# ELEKTRA-PMIC_v0_2-Ful_frame_shield_-35X2.net
KiCad netlist of a schematic drawn in EAGLE
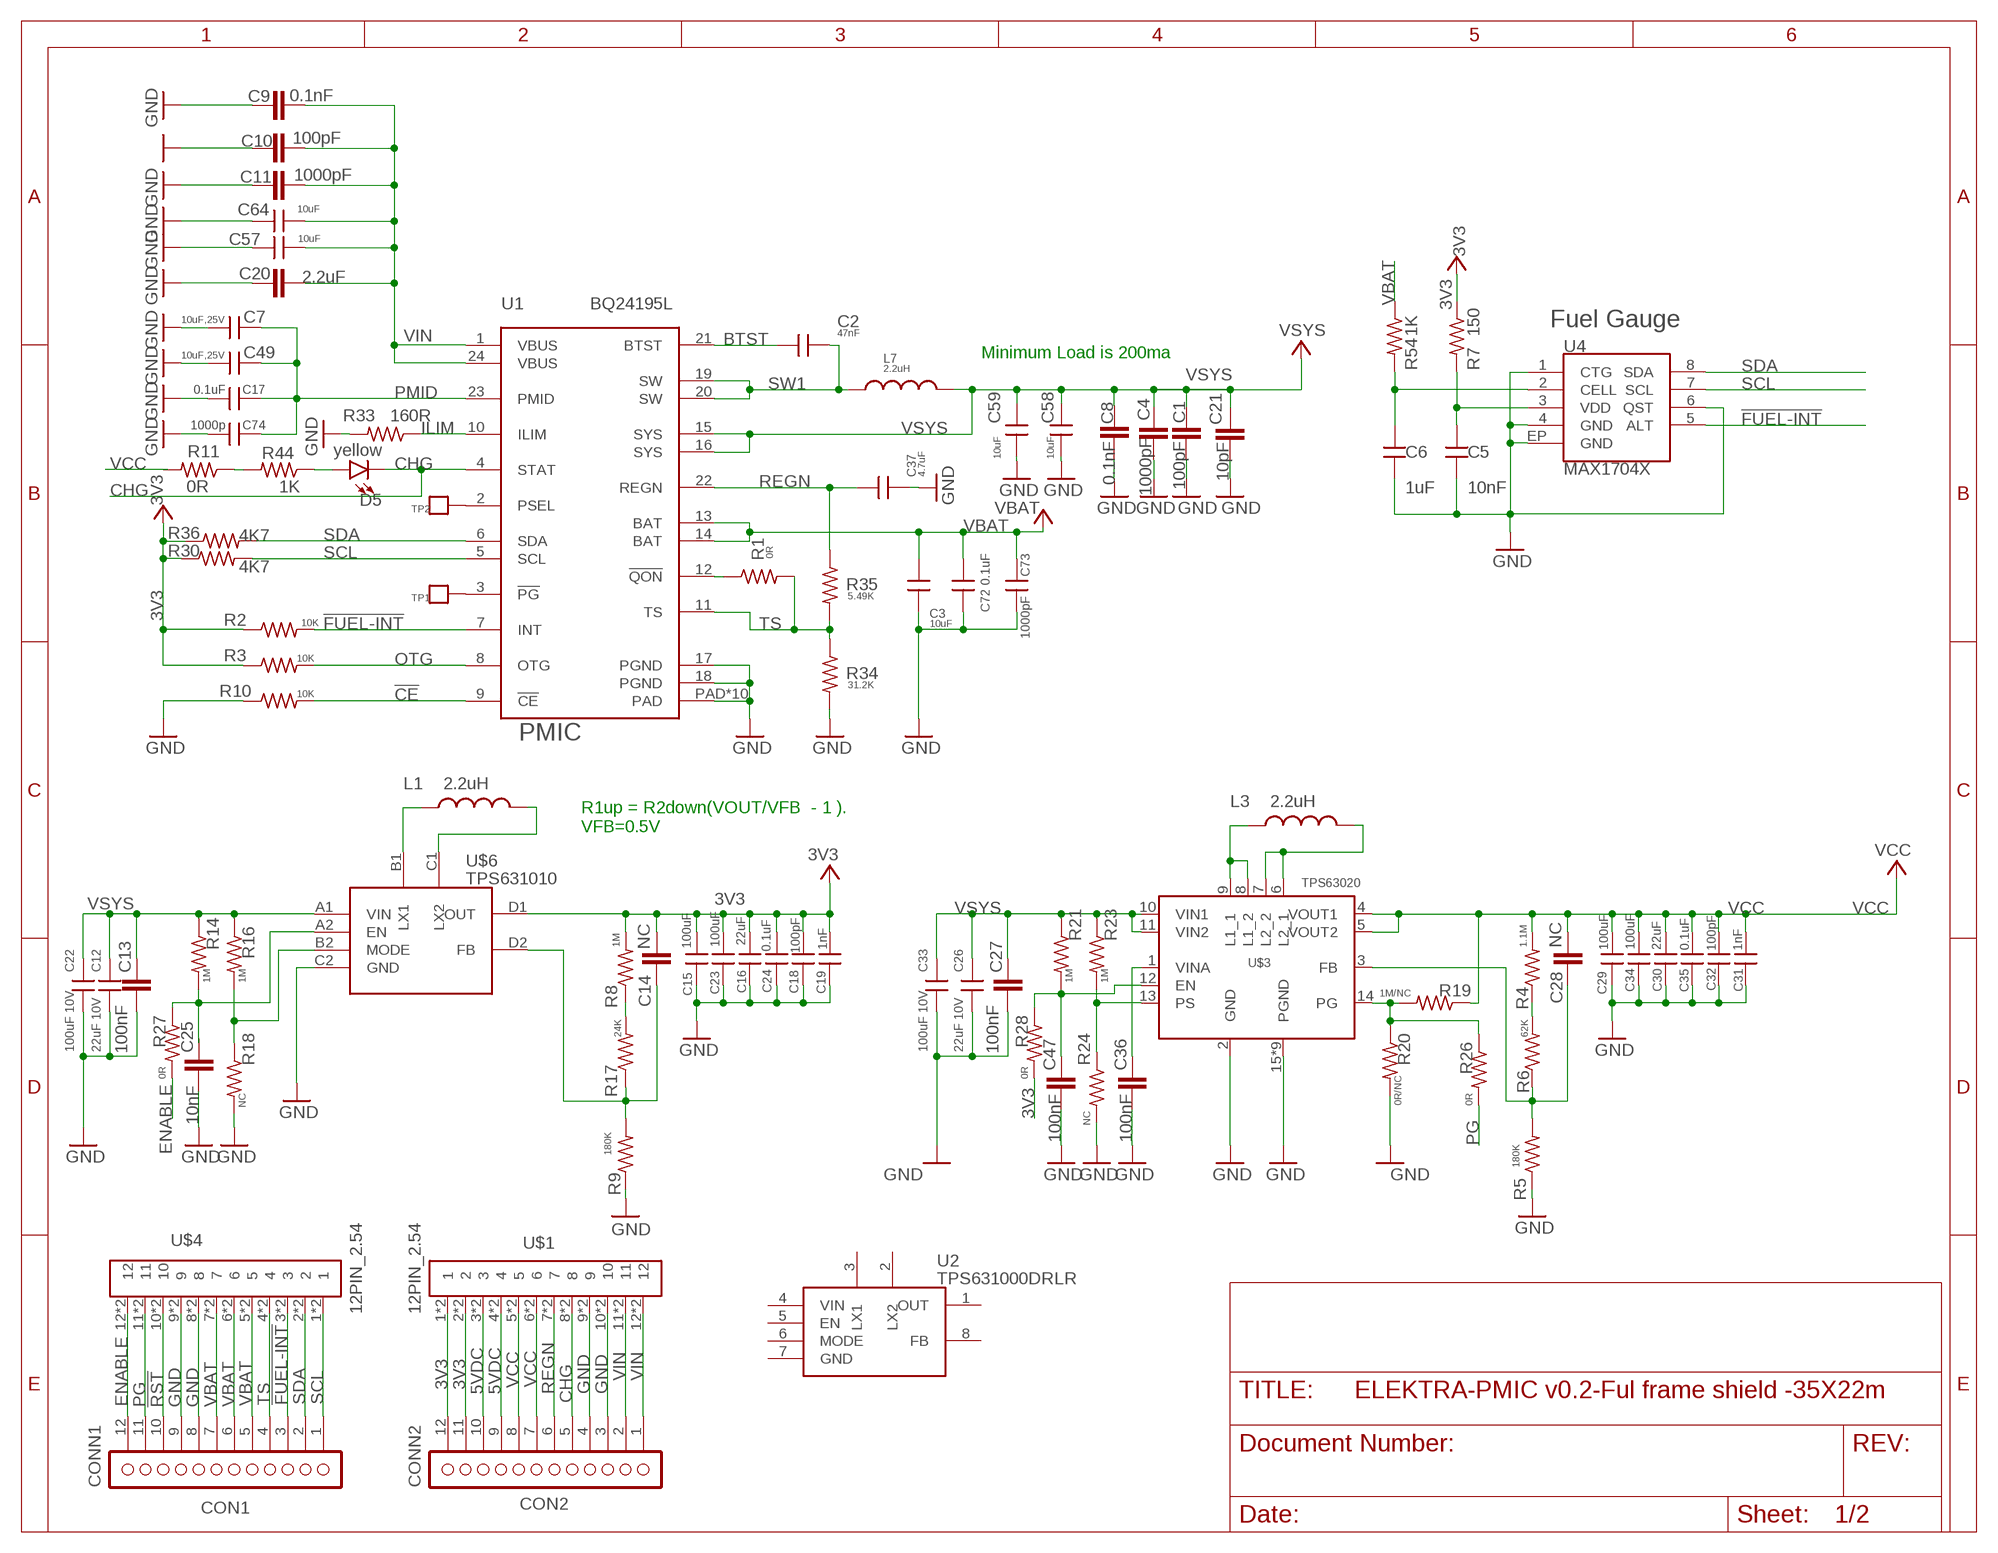
[diagram p0: schematic, sheet 1]

(export (version "E")
  (design (tool "Eeschema 10.0.6"))
  (components
    (comp (ref "C1")
      (value "100pF")
      (footprint "eagle-import:C0402_B")
      (libsource (lib "eagle-import") (part "CAP_1"))
    )
    (comp (ref "C2")
      (value "47nF")
      (footprint "eagle-import:C-0402")
      (libsource (lib "eagle-import") (part "particle SZ_CAP0402"))
    )
    (comp (ref "C3")
      (value "10uF")
      (footprint "eagle-import:C0603")
      (libsource (lib "eagle-import") (part "particle SZ_CAPC0603"))
    )
    (comp (ref "C4")
      (value "1000pF")
      (footprint "eagle-import:C0402_B")
      (libsource (lib "eagle-import") (part "CAP_1"))
    )
    (comp (ref "C5")
      (value "10nF")
      (footprint "eagle-import:C0402")
      (libsource (lib "eagle-import") (part "particle SZ_CAP0402A"))
    )
    (comp (ref "C6")
      (value "1uF")
      (footprint "eagle-import:C0402")
      (libsource (lib "eagle-import") (part "particle SZ_CAP0402A"))
    )
    (comp (ref "C7")
      (value "10uF,25V")
      (footprint "eagle-import:C-0603A")
      (libsource (lib "eagle-import") (part "particle SZ_CAP0603A"))
    )
    (comp (ref "C8")
      (value "0.1nF")
      (footprint "eagle-import:C0402_B")
      (libsource (lib "eagle-import") (part "CAP_1"))
    )
    (comp (ref "C9")
      (value "0.1nF")
      (footprint "eagle-import:C0402_B")
      (libsource (lib "eagle-import") (part "CAP_1"))
    )
    (comp (ref "C10")
      (value "100pF")
      (footprint "eagle-import:C0402_B")
      (libsource (lib "eagle-import") (part "CAP_1"))
    )
    (comp (ref "C11")
      (value "1000pF")
      (footprint "eagle-import:C0402_B")
      (libsource (lib "eagle-import") (part "CAP_1"))
    )
    (comp (ref "C12")
      (value "22uF 10V")
      (footprint "eagle-import:C0805")
      (libsource (lib "eagle-import") (part "particle SZ_21650216_CAPC0805"))
    )
    (comp (ref "C13")
      (value "100nF")
      (footprint "eagle-import:C0402_B")
      (libsource (lib "eagle-import") (part "CAP_1"))
    )
    (comp (ref "C14")
      (value "NC")
      (footprint "eagle-import:C0402_B")
      (libsource (lib "eagle-import") (part "CAP_1"))
    )
    (comp (ref "C15")
      (value "100uF")
      (footprint "eagle-import:C1206")
      (libsource (lib "eagle-import") (part "particle SZ_21650216_CAPC1206"))
    )
    (comp (ref "C16")
      (value "22uF")
      (footprint "eagle-import:C-0603A")
      (libsource (lib "eagle-import") (part "particle SZ_21650216_CAP0603A"))
    )
    (comp (ref "C17")
      (value "0.1uF")
      (footprint "eagle-import:C0402")
      (libsource (lib "eagle-import") (part "CAP0402A"))
    )
    (comp (ref "C18")
      (value "100pF")
      (footprint "eagle-import:C0402")
      (libsource (lib "eagle-import") (part "particle SZ_CAP0402A"))
    )
    (comp (ref "C19")
      (value "1nF")
      (footprint "eagle-import:C0402")
      (libsource (lib "eagle-import") (part "particle SZ_CAP0402A"))
    )
    (comp (ref "C20")
      (value "2.2uF")
      (footprint "eagle-import:C0402_B")
      (libsource (lib "eagle-import") (part "CAP_1"))
    )
    (comp (ref "C21")
      (value "10pF")
      (footprint "eagle-import:C0402_B")
      (libsource (lib "eagle-import") (part "CAP_1"))
    )
    (comp (ref "C22")
      (value "100uF 10V")
      (footprint "eagle-import:C1206")
      (libsource (lib "eagle-import") (part "particle SZ_21650216_CAPC1206"))
    )
    (comp (ref "C23")
      (value "100uF")
      (footprint "eagle-import:C1206")
      (libsource (lib "eagle-import") (part "particle SZ_21650216_CAPC1206"))
    )
    (comp (ref "C24")
      (value "0.1uF")
      (footprint "eagle-import:C0402")
      (libsource (lib "eagle-import") (part "particle SZ_CAP0402A"))
    )
    (comp (ref "C25")
      (value "10nF")
      (footprint "eagle-import:C0402_B")
      (libsource (lib "eagle-import") (part "CAP_1"))
    )
    (comp (ref "C26")
      (value "22uF 10V")
      (footprint "eagle-import:C0805")
      (libsource (lib "eagle-import") (part "particle SZ_21650216_CAPC0805"))
    )
    (comp (ref "C27")
      (value "100nF")
      (footprint "eagle-import:C0402_B")
      (libsource (lib "eagle-import") (part "CAP_1"))
    )
    (comp (ref "C28")
      (value "NC")
      (footprint "eagle-import:C0402_B")
      (libsource (lib "eagle-import") (part "CAP_1"))
    )
    (comp (ref "C29")
      (value "100uF")
      (footprint "eagle-import:C1206")
      (libsource (lib "eagle-import") (part "particle SZ_21650216_CAPC1206"))
    )
    (comp (ref "C30")
      (value "22uF")
      (footprint "eagle-import:C-0603A")
      (libsource (lib "eagle-import") (part "particle SZ_21650216_CAP0603A"))
    )
    (comp (ref "C31")
      (value "1nF")
      (footprint "eagle-import:C0402")
      (libsource (lib "eagle-import") (part "particle SZ_CAP0402A"))
    )
    (comp (ref "C32")
      (value "100pF")
      (footprint "eagle-import:C0402")
      (libsource (lib "eagle-import") (part "particle SZ_CAP0402A"))
    )
    (comp (ref "C33")
      (value "100uF 10V")
      (footprint "eagle-import:C1206")
      (libsource (lib "eagle-import") (part "particle SZ_21650216_CAPC1206"))
    )
    (comp (ref "C34")
      (value "100uF")
      (footprint "eagle-import:C1206")
      (libsource (lib "eagle-import") (part "particle SZ_21650216_CAPC1206"))
    )
    (comp (ref "C35")
      (value "0.1uF")
      (footprint "eagle-import:C0402")
      (libsource (lib "eagle-import") (part "particle SZ_CAP0402A"))
    )
    (comp (ref "C36")
      (value "100nF")
      (footprint "eagle-import:C0402_B")
      (libsource (lib "eagle-import") (part "CAP_1"))
    )
    (comp (ref "C37")
      (value "4.7uF")
      (footprint "eagle-import:C0402")
      (libsource (lib "eagle-import") (part "particle SZ_CAP0402A"))
    )
    (comp (ref "C47")
      (value "100nF")
      (footprint "eagle-import:C0402_B")
      (libsource (lib "eagle-import") (part "CAP_1"))
    )
    (comp (ref "C49")
      (value "10uF,25V")
      (footprint "eagle-import:C-0603A")
      (libsource (lib "eagle-import") (part "particle SZ_CAP0603A"))
    )
    (comp (ref "C57")
      (value "10uF")
      (footprint "eagle-import:C-0603A")
      (libsource (lib "eagle-import") (part "particle SZ_CAP0603A"))
    )
    (comp (ref "C58")
      (value "10uF")
      (footprint "eagle-import:C-0603A")
      (libsource (lib "eagle-import") (part "particle SZ_CAP0603A"))
    )
    (comp (ref "C59")
      (value "10uF")
      (footprint "eagle-import:C-0603A")
      (libsource (lib "eagle-import") (part "particle SZ_CAP0603A"))
    )
    (comp (ref "C64")
      (value "10uF")
      (footprint "eagle-import:C-0603A")
      (libsource (lib "eagle-import") (part "particle SZ_CAP0603A"))
    )
    (comp (ref "C72")
      (value "0.1uF")
      (footprint "eagle-import:C-0402")
      (libsource (lib "eagle-import") (part "particle SZ_CAP0402"))
    )
    (comp (ref "C73")
      (value "1000pF")
      (footprint "eagle-import:C-0402")
      (libsource (lib "eagle-import") (part "particle SZ_CAP0402"))
    )
    (comp (ref "C74")
      (value "1000p")
      (footprint "eagle-import:C-0402")
      (libsource (lib "eagle-import") (part "particle SZ_CAP0402"))
    )
    (comp (ref "CONN1")
      (value "CON1")
      (footprint "eagle-import:1X12_SMD_STRAIGHT")
      (libsource (lib "eagle-import") (part "CONN12"))
    )
    (comp (ref "CONN2")
      (value "CON2")
      (footprint "eagle-import:1X12_SMD_STRAIGHT")
      (libsource (lib "eagle-import") (part "CONN12"))
    )
    (comp (ref "D5")
      (value "yellow")
      (footprint "eagle-import:LED-0603")
      (libsource (lib "eagle-import") (part "LED-RED0603"))
    )
    (comp (ref "L1")
      (value "2.2uH")
      (footprint "eagle-import:INDUCTOR-VLS-E")
      (libsource (lib "eagle-import") (part "INDUCTOR-SPARKFUNVLS3012ET-4R7M"))
    )
    (comp (ref "L3")
      (value "2.2uH")
      (footprint "eagle-import:INDUCTOR-VLS-E")
      (libsource (lib "eagle-import") (part "INDUCTOR-SPARKFUNVLS3012ET-4R7M"))
    )
    (comp (ref "L7")
      (value "2.2uH")
      (footprint "eagle-import:INDUCTOR-4040")
      (libsource (lib "eagle-import") (part "INDUCTORI"))
    )
    (comp (ref "R1")
      (value "0R")
      (footprint "eagle-import:R0402_B")
      (libsource (lib "eagle-import") (part "Spark_R-US_"))
    )
    (comp (ref "R2")
      (value "10K")
      (footprint "eagle-import:R0402_B")
      (libsource (lib "eagle-import") (part "Spark_R-US_"))
    )
    (comp (ref "R3")
      (value "10K")
      (footprint "eagle-import:R0402_B")
      (libsource (lib "eagle-import") (part "Spark_R-US_"))
    )
    (comp (ref "R4")
      (value "1.1M")
      (footprint "eagle-import:R0402_B")
      (libsource (lib "eagle-import") (part "Spark_R-US_"))
    )
    (comp (ref "R5")
      (value "180K")
      (footprint "eagle-import:R0402_B")
      (libsource (lib "eagle-import") (part "Spark_R-US_"))
    )
    (comp (ref "R6")
      (value "62K")
      (footprint "eagle-import:R0402_B")
      (libsource (lib "eagle-import") (part "Spark_R-US_"))
    )
    (comp (ref "R7")
      (value "150")
      (footprint "eagle-import:R0402_B")
      (libsource (lib "eagle-import") (part "R-US_"))
    )
    (comp (ref "R8")
      (value "1M")
      (footprint "eagle-import:R0402_B")
      (libsource (lib "eagle-import") (part "Spark_R-US_"))
    )
    (comp (ref "R9")
      (value "180K")
      (footprint "eagle-import:R0402_B")
      (libsource (lib "eagle-import") (part "Spark_R-US_"))
    )
    (comp (ref "R10")
      (value "10K")
      (footprint "eagle-import:R0402_B")
      (libsource (lib "eagle-import") (part "Spark_R-US_"))
    )
    (comp (ref "R11")
      (value "0R")
      (footprint "eagle-import:R0402_B")
      (libsource (lib "eagle-import") (part "R-US_"))
    )
    (comp (ref "R14")
      (value "1M")
      (footprint "eagle-import:R0402_B")
      (libsource (lib "eagle-import") (part "Spark_R-US_"))
    )
    (comp (ref "R16")
      (value "1M")
      (footprint "eagle-import:R0402_B")
      (libsource (lib "eagle-import") (part "Spark_R-US_"))
    )
    (comp (ref "R17")
      (value "24K")
      (footprint "eagle-import:R0402_B")
      (libsource (lib "eagle-import") (part "Spark_R-US_"))
    )
    (comp (ref "R18")
      (value "NC")
      (footprint "eagle-import:R0402_B")
      (libsource (lib "eagle-import") (part "Spark_R-US_"))
    )
    (comp (ref "R19")
      (value "1M/NC")
      (footprint "eagle-import:R0402_B")
      (libsource (lib "eagle-import") (part "Spark_R-US_"))
    )
    (comp (ref "R20")
      (value "0R/NC")
      (footprint "eagle-import:R0402_B")
      (libsource (lib "eagle-import") (part "Spark_R-US_"))
    )
    (comp (ref "R21")
      (value "1M")
      (footprint "eagle-import:R0402_B")
      (libsource (lib "eagle-import") (part "Spark_R-US_"))
    )
    (comp (ref "R23")
      (value "1M")
      (footprint "eagle-import:R0402_B")
      (libsource (lib "eagle-import") (part "Spark_R-US_"))
    )
    (comp (ref "R24")
      (value "NC")
      (footprint "eagle-import:R0402_B")
      (libsource (lib "eagle-import") (part "Spark_R-US_"))
    )
    (comp (ref "R26")
      (value "0R")
      (footprint "eagle-import:R0402_B")
      (libsource (lib "eagle-import") (part "Spark_R-US_"))
    )
    (comp (ref "R27")
      (value "0R")
      (footprint "eagle-import:R0402_B")
      (libsource (lib "eagle-import") (part "Spark_R-US_"))
    )
    (comp (ref "R28")
      (value "0R")
      (footprint "eagle-import:R0402_B")
      (libsource (lib "eagle-import") (part "Spark_R-US_"))
    )
    (comp (ref "R30")
      (value "4K7")
      (footprint "eagle-import:R0402_B")
      (libsource (lib "eagle-import") (part "R-US_"))
    )
    (comp (ref "R33")
      (value "160R")
      (footprint "eagle-import:R0402_B")
      (libsource (lib "eagle-import") (part "R-US_"))
    )
    (comp (ref "R34")
      (value "31.2K")
      (footprint "eagle-import:R0402_B")
      (libsource (lib "eagle-import") (part "Spark_R-US_"))
    )
    (comp (ref "R35")
      (value "5.49K")
      (footprint "eagle-import:R0402_B")
      (libsource (lib "eagle-import") (part "Spark_R-US_"))
    )
    (comp (ref "R36")
      (value "4K7")
      (footprint "eagle-import:R0402_B")
      (libsource (lib "eagle-import") (part "R-US_"))
    )
    (comp (ref "R44")
      (value "1K")
      (footprint "eagle-import:R0402_B")
      (libsource (lib "eagle-import") (part "R-US_"))
    )
    (comp (ref "R54")
      (value "1K")
      (footprint "eagle-import:R0402_B")
      (libsource (lib "eagle-import") (part "R-US_"))
    )
    (comp (ref "TP1")
      (value "TP")
      (footprint "eagle-import:TP0.7MM")
      (libsource (lib "eagle-import") (part "TP"))
    )
    (comp (ref "TP2")
      (value "TP")
      (footprint "eagle-import:TP0.7MM")
      (libsource (lib "eagle-import") (part "TP"))
    )
    (comp (ref "U$1")
      (value "12PIN_2.54")
      (footprint "eagle-import:12PIN_2.54")
      (libsource (lib "eagle-import") (part "12PIN_2.54"))
    )
    (comp (ref "U$3")
      (value "TPS63020")
      (footprint "eagle-import:TPS63020")
      (libsource (lib "eagle-import") (part "TPS63020"))
    )
    (comp (ref "U$4")
      (value "12PIN_2.54")
      (footprint "eagle-import:12PIN_2.54")
      (libsource (lib "eagle-import") (part "12PIN_2.54"))
    )
    (comp (ref "U$6")
      (value "TPS631010")
      (footprint "eagle-import:DSBGA")
      (libsource (lib "eagle-import") (part "TPS631010"))
    )
    (comp (ref "U1")
      (value "BQ24195L")
      (footprint "eagle-import:QFN24")
      (libsource (lib "eagle-import") (part "BQ24298RTWR"))
    )
    (comp (ref "U2")
      (value "TPS631000DRLR")
      (footprint "eagle-import:SOT538")
      (libsource (lib "eagle-import") (part "TPS631000DRLR"))
    )
    (comp (ref "U4")
      (value "MAX1704X")
      (footprint "eagle-import:TDFN-8")
      (libsource (lib "eagle-import") (part "MAX1704X"))
    )
  )
  (nets
    (net (code "1") (name "3V3") (class "Default")
      (node (ref "C14") (pin "2") (pinfunction "P$2_2") (pintype "passive"))
      (node (ref "C15") (pin "1") (pinfunction "1_1") (pintype "bidirectional"))
      (node (ref "C16") (pin "1") (pinfunction "1_1") (pintype "bidirectional"))
      (node (ref "C18") (pin "1") (pinfunction "1_1") (pintype "bidirectional"))
      (node (ref "C19") (pin "1") (pinfunction "1_1") (pintype "bidirectional"))
      (node (ref "C23") (pin "1") (pinfunction "1_1") (pintype "bidirectional"))
      (node (ref "C24") (pin "1") (pinfunction "1_1") (pintype "bidirectional"))
      (node (ref "CONN2") (pin "11") (pinfunction "11_11") (pintype "passive"))
      (node (ref "CONN2") (pin "12") (pinfunction "12_12") (pintype "passive"))
      (node (ref "R2") (pin "1") (pinfunction "1_1") (pintype "passive"))
      (node (ref "R28") (pin "2") (pinfunction "2_2") (pintype "passive"))
      (node (ref "R3") (pin "1") (pinfunction "1_1") (pintype "passive"))
      (node (ref "R30") (pin "1") (pinfunction "1_1") (pintype "passive"))
      (node (ref "R36") (pin "1") (pinfunction "1_1") (pintype "passive"))
      (node (ref "R7") (pin "1") (pinfunction "1_1") (pintype "passive"))
      (node (ref "R8") (pin "2") (pinfunction "2_2") (pintype "passive"))
      (node (ref "U$1") (pin "1") (pinfunction "1_1") (pintype "bidirectional"))
      (node (ref "U$1") (pin "2") (pinfunction "2_2") (pintype "bidirectional"))
      (node (ref "U$1") (pin "P$1") (pinfunction "1_P$1") (pintype "bidirectional"))
      (node (ref "U$1") (pin "P$2") (pinfunction "2_P$2") (pintype "bidirectional"))
      (node (ref "U$6") (pin "D1") (pinfunction "OUT_D1") (pintype "bidirectional"))
    )
    (net (code "2") (name "5VDC") (class "Default")
      (node (ref "CONN2") (pin "10") (pinfunction "10_10") (pintype "passive"))
      (node (ref "CONN2") (pin "9") (pinfunction "9_9") (pintype "passive"))
      (node (ref "U$1") (pin "3") (pinfunction "3_3") (pintype "bidirectional"))
      (node (ref "U$1") (pin "4") (pinfunction "4_4") (pintype "bidirectional"))
      (node (ref "U$1") (pin "P$3") (pinfunction "3_P$3") (pintype "bidirectional"))
      (node (ref "U$1") (pin "P$4") (pinfunction "4_P$4") (pintype "bidirectional"))
    )
    (net (code "3") (name "BTST") (class "Default")
      (node (ref "C2") (pin "1") (pinfunction "1_1") (pintype "bidirectional"))
      (node (ref "U1") (pin "21") (pinfunction "BTST_21") (pintype "bidirectional"))
    )
    (net (code "4") (name "CHG") (class "Default")
      (node (ref "CONN2") (pin "5") (pinfunction "5_5") (pintype "passive"))
      (node (ref "D5") (pin "C") (pinfunction "C_C") (pintype "passive"))
      (node (ref "U$1") (pin "8") (pinfunction "8_8") (pintype "bidirectional"))
      (node (ref "U$1") (pin "P$8") (pinfunction "8_P$8") (pintype "bidirectional"))
      (node (ref "U1") (pin "4") (pinfunction "STAT_4") (pintype "bidirectional"))
    )
    (net (code "5") (name "ENABLE") (class "Default")
      (node (ref "CONN1") (pin "12") (pinfunction "12_12") (pintype "passive"))
      (node (ref "R27") (pin "2") (pinfunction "2_2") (pintype "passive"))
      (node (ref "U$4") (pin "12") (pinfunction "12_12") (pintype "bidirectional"))
      (node (ref "U$4") (pin "P$12") (pinfunction "12_P$12") (pintype "bidirectional"))
    )
    (net (code "6") (name "GND") (class "Default")
      (node (ref "C1") (pin "1") (pinfunction "P$1_1") (pintype "passive"))
      (node (ref "C10") (pin "1") (pinfunction "P$1_1") (pintype "passive"))
      (node (ref "C11") (pin "1") (pinfunction "P$1_1") (pintype "passive"))
      (node (ref "C12") (pin "2") (pinfunction "2_2") (pintype "bidirectional"))
      (node (ref "C13") (pin "1") (pinfunction "P$1_1") (pintype "passive"))
      (node (ref "C15") (pin "2") (pinfunction "2_2") (pintype "bidirectional"))
      (node (ref "C16") (pin "2") (pinfunction "2_2") (pintype "bidirectional"))
      (node (ref "C17") (pin "1") (pinfunction "1_1") (pintype "bidirectional"))
      (node (ref "C18") (pin "2") (pinfunction "2_2") (pintype "bidirectional"))
      (node (ref "C19") (pin "2") (pinfunction "2_2") (pintype "bidirectional"))
      (node (ref "C20") (pin "1") (pinfunction "P$1_1") (pintype "passive"))
      (node (ref "C21") (pin "1") (pinfunction "P$1_1") (pintype "passive"))
      (node (ref "C22") (pin "2") (pinfunction "2_2") (pintype "bidirectional"))
      (node (ref "C23") (pin "2") (pinfunction "2_2") (pintype "bidirectional"))
      (node (ref "C24") (pin "2") (pinfunction "2_2") (pintype "bidirectional"))
      (node (ref "C25") (pin "1") (pinfunction "P$1_1") (pintype "passive"))
      (node (ref "C26") (pin "2") (pinfunction "2_2") (pintype "bidirectional"))
      (node (ref "C27") (pin "1") (pinfunction "P$1_1") (pintype "passive"))
      (node (ref "C29") (pin "2") (pinfunction "2_2") (pintype "bidirectional"))
      (node (ref "C3") (pin "2") (pinfunction "2_2") (pintype "bidirectional"))
      (node (ref "C30") (pin "2") (pinfunction "2_2") (pintype "bidirectional"))
      (node (ref "C31") (pin "2") (pinfunction "2_2") (pintype "bidirectional"))
      (node (ref "C32") (pin "2") (pinfunction "2_2") (pintype "bidirectional"))
      (node (ref "C33") (pin "2") (pinfunction "2_2") (pintype "bidirectional"))
      (node (ref "C34") (pin "2") (pinfunction "2_2") (pintype "bidirectional"))
      (node (ref "C35") (pin "2") (pinfunction "2_2") (pintype "bidirectional"))
      (node (ref "C36") (pin "1") (pinfunction "P$1_1") (pintype "passive"))
      (node (ref "C37") (pin "2") (pinfunction "2_2") (pintype "bidirectional"))
      (node (ref "C4") (pin "1") (pinfunction "P$1_1") (pintype "passive"))
      (node (ref "C47") (pin "1") (pinfunction "P$1_1") (pintype "passive"))
      (node (ref "C49") (pin "2") (pinfunction "2_2") (pintype "bidirectional"))
      (node (ref "C5") (pin "2") (pinfunction "2_2") (pintype "bidirectional"))
      (node (ref "C57") (pin "2") (pinfunction "2_2") (pintype "bidirectional"))
      (node (ref "C58") (pin "2") (pinfunction "2_2") (pintype "bidirectional"))
      (node (ref "C59") (pin "2") (pinfunction "2_2") (pintype "bidirectional"))
      (node (ref "C6") (pin "2") (pinfunction "2_2") (pintype "bidirectional"))
      (node (ref "C64") (pin "2") (pinfunction "2_2") (pintype "bidirectional"))
      (node (ref "C7") (pin "2") (pinfunction "2_2") (pintype "bidirectional"))
      (node (ref "C72") (pin "2") (pinfunction "2_2") (pintype "bidirectional"))
      (node (ref "C73") (pin "2") (pinfunction "2_2") (pintype "bidirectional"))
      (node (ref "C74") (pin "1") (pinfunction "1_1") (pintype "bidirectional"))
      (node (ref "C8") (pin "1") (pinfunction "P$1_1") (pintype "passive"))
      (node (ref "C9") (pin "1") (pinfunction "P$1_1") (pintype "passive"))
      (node (ref "CONN1") (pin "8") (pinfunction "8_8") (pintype "passive"))
      (node (ref "CONN1") (pin "9") (pinfunction "9_9") (pintype "passive"))
      (node (ref "CONN2") (pin "3") (pinfunction "3_3") (pintype "passive"))
      (node (ref "CONN2") (pin "4") (pinfunction "4_4") (pintype "passive"))
      (node (ref "R10") (pin "1") (pinfunction "1_1") (pintype "passive"))
      (node (ref "R18") (pin "2") (pinfunction "2_2") (pintype "passive"))
      (node (ref "R20") (pin "2") (pinfunction "2_2") (pintype "passive"))
      (node (ref "R24") (pin "2") (pinfunction "2_2") (pintype "passive"))
      (node (ref "R33") (pin "2") (pinfunction "2_2") (pintype "passive"))
      (node (ref "R34") (pin "2") (pinfunction "2_2") (pintype "passive"))
      (node (ref "R5") (pin "1") (pinfunction "1_1") (pintype "passive"))
      (node (ref "R9") (pin "1") (pinfunction "1_1") (pintype "passive"))
      (node (ref "U$1") (pin "10") (pinfunction "10_10") (pintype "bidirectional"))
      (node (ref "U$1") (pin "9") (pinfunction "9_9") (pintype "bidirectional"))
      (node (ref "U$1") (pin "P$10") (pinfunction "10_P$10") (pintype "bidirectional"))
      (node (ref "U$1") (pin "P$9") (pinfunction "9_P$9") (pintype "bidirectional"))
      (node (ref "U$3") (pin "15") (pinfunction "PGND_15") (pintype "bidirectional"))
      (node (ref "U$3") (pin "16") (pinfunction "PGND_16") (pintype "bidirectional"))
      (node (ref "U$3") (pin "17") (pinfunction "PGND_17") (pintype "bidirectional"))
      (node (ref "U$3") (pin "18") (pinfunction "PGND_18") (pintype "bidirectional"))
      (node (ref "U$3") (pin "19") (pinfunction "PGND_19") (pintype "bidirectional"))
      (node (ref "U$3") (pin "2") (pinfunction "GND_2") (pintype "bidirectional"))
      (node (ref "U$3") (pin "20") (pinfunction "PGND_20") (pintype "bidirectional"))
      (node (ref "U$3") (pin "21") (pinfunction "PGND_21") (pintype "bidirectional"))
      (node (ref "U$3") (pin "22") (pinfunction "PGND_22") (pintype "bidirectional"))
      (node (ref "U$3") (pin "23") (pinfunction "PGND_23") (pintype "bidirectional"))
      (node (ref "U$4") (pin "8") (pinfunction "8_8") (pintype "bidirectional"))
      (node (ref "U$4") (pin "9") (pinfunction "9_9") (pintype "bidirectional"))
      (node (ref "U$4") (pin "P$8") (pinfunction "8_P$8") (pintype "bidirectional"))
      (node (ref "U$4") (pin "P$9") (pinfunction "9_P$9") (pintype "bidirectional"))
      (node (ref "U$6") (pin "C2") (pinfunction "GND_C2") (pintype "bidirectional"))
      (node (ref "U1") (pin "17") (pinfunction "PGND_17") (pintype "passive"))
      (node (ref "U1") (pin "18") (pinfunction "PGND_18") (pintype "passive"))
      (node (ref "U1") (pin "PAD") (pinfunction "PAD_PAD") (pintype "power_in"))
      (node (ref "U1") (pin "PAD@1") (pinfunction "PAD_PAD@1") (pintype "power_in"))
      (node (ref "U1") (pin "PAD@2") (pinfunction "PAD_PAD@2") (pintype "power_in"))
      (node (ref "U1") (pin "PAD@3") (pinfunction "PAD_PAD@3") (pintype "power_in"))
      (node (ref "U1") (pin "PAD@4") (pinfunction "PAD_PAD@4") (pintype "power_in"))
      (node (ref "U1") (pin "PAD@5") (pinfunction "PAD_PAD@5") (pintype "power_in"))
      (node (ref "U1") (pin "PAD@6") (pinfunction "PAD_PAD@6") (pintype "power_in"))
      (node (ref "U1") (pin "PAD@7") (pinfunction "PAD_PAD@7") (pintype "power_in"))
      (node (ref "U1") (pin "PAD@8") (pinfunction "PAD_PAD@8") (pintype "power_in"))
      (node (ref "U1") (pin "PAD@9") (pinfunction "PAD_PAD@9") (pintype "power_in"))
      (node (ref "U4") (pin "1") (pinfunction "CTG_1") (pintype "bidirectional"))
      (node (ref "U4") (pin "4") (pinfunction "GND_4") (pintype "bidirectional"))
      (node (ref "U4") (pin "6") (pinfunction "QST_6") (pintype "bidirectional"))
      (node (ref "U4") (pin "EP") (pinfunction "GND_EP") (pintype "bidirectional"))
    )
    (net (code "7") (name "ILIM") (class "Default")
      (node (ref "R33") (pin "1") (pinfunction "1_1") (pintype "passive"))
      (node (ref "U1") (pin "10") (pinfunction "ILIM_10") (pintype "output"))
    )
    (net (code "8") (name "Net-(C14-P$1)") (class "Default")
      (node (ref "C14") (pin "1") (pinfunction "P$1_1") (pintype "passive"))
      (node (ref "R17") (pin "1") (pinfunction "1_1") (pintype "passive"))
      (node (ref "R9") (pin "2") (pinfunction "2_2") (pintype "passive"))
      (node (ref "U$6") (pin "D2") (pinfunction "FB_D2") (pintype "bidirectional"))
    )
    (net (code "9") (name "Net-(C25-P$2)") (class "Default")
      (node (ref "C25") (pin "2") (pinfunction "P$2_2") (pintype "passive"))
      (node (ref "R14") (pin "2") (pinfunction "2_2") (pintype "passive"))
      (node (ref "R27") (pin "1") (pinfunction "1_1") (pintype "passive"))
      (node (ref "U$6") (pin "A2") (pinfunction "EN_A2") (pintype "bidirectional"))
    )
    (net (code "10") (name "Net-(C28-P$1)") (class "Default")
      (node (ref "C28") (pin "1") (pinfunction "P$1_1") (pintype "passive"))
      (node (ref "R5") (pin "2") (pinfunction "2_2") (pintype "passive"))
      (node (ref "R6") (pin "1") (pinfunction "1_1") (pintype "passive"))
      (node (ref "U$3") (pin "3") (pinfunction "FB_3") (pintype "bidirectional"))
    )
    (net (code "11") (name "Net-(C36-P$2)") (class "Default")
      (node (ref "C36") (pin "2") (pinfunction "P$2_2") (pintype "passive"))
      (node (ref "U$3") (pin "1") (pinfunction "VINA_1") (pintype "bidirectional"))
    )
    (net (code "12") (name "Net-(C47-P$2)") (class "Default")
      (node (ref "C47") (pin "2") (pinfunction "P$2_2") (pintype "passive"))
      (node (ref "R21") (pin "2") (pinfunction "2_2") (pintype "passive"))
      (node (ref "R28") (pin "1") (pinfunction "1_1") (pintype "passive"))
      (node (ref "U$3") (pin "12") (pinfunction "EN_12") (pintype "bidirectional"))
    )
    (net (code "13") (name "Net-(D5-PadA)") (class "Default")
      (node (ref "D5") (pin "A") (pinfunction "A_A") (pintype "passive"))
      (node (ref "R44") (pin "1") (pinfunction "1_1") (pintype "passive"))
    )
    (net (code "14") (name "Net-(L1-1)") (class "Default")
      (node (ref "L1") (pin "P$1") (pinfunction "1_P$1") (pintype "passive"))
      (node (ref "U$6") (pin "B1") (pinfunction "LX1_B1") (pintype "bidirectional"))
    )
    (net (code "15") (name "Net-(L1-2)") (class "Default")
      (node (ref "L1") (pin "P$2") (pinfunction "2_P$2") (pintype "passive"))
      (node (ref "U$6") (pin "C1") (pinfunction "LX2_C1") (pintype "bidirectional"))
    )
    (net (code "16") (name "Net-(L3-1)") (class "Default")
      (node (ref "L3") (pin "P$1") (pinfunction "1_P$1") (pintype "passive"))
      (node (ref "U$3") (pin "8") (pinfunction "L1_2_8") (pintype "bidirectional"))
      (node (ref "U$3") (pin "9") (pinfunction "L1_1_9") (pintype "bidirectional"))
    )
    (net (code "17") (name "Net-(L3-2)") (class "Default")
      (node (ref "L3") (pin "P$2") (pinfunction "2_P$2") (pintype "passive"))
      (node (ref "U$3") (pin "6") (pinfunction "L2_1_6") (pintype "bidirectional"))
      (node (ref "U$3") (pin "7") (pinfunction "L2_2_7") (pintype "bidirectional"))
    )
    (net (code "18") (name "Net-(R4-Pad1)") (class "Default")
      (node (ref "R4") (pin "1") (pinfunction "1_1") (pintype "passive"))
      (node (ref "R6") (pin "2") (pinfunction "2_2") (pintype "passive"))
    )
    (net (code "19") (name "Net-(R11-Pad1)") (class "Default")
      (node (ref "R11") (pin "1") (pinfunction "1_1") (pintype "passive"))
      (node (ref "R44") (pin "2") (pinfunction "2_2") (pintype "passive"))
    )
    (net (code "20") (name "Net-(R17-Pad2)") (class "Default")
      (node (ref "R17") (pin "2") (pinfunction "2_2") (pintype "passive"))
      (node (ref "R8") (pin "1") (pinfunction "1_1") (pintype "passive"))
    )
    (net (code "21") (name "Net-(TP1-1)") (class "Default")
      (node (ref "TP1") (pin "P$1") (pinfunction "1_P$1") (pintype "bidirectional"))
      (node (ref "U1") (pin "3") (pinfunction "~{PG}_3") (pintype "output"))
    )
    (net (code "22") (name "Net-(TP2-1)") (class "Default")
      (node (ref "TP2") (pin "P$1") (pinfunction "1_P$1") (pintype "bidirectional"))
      (node (ref "U1") (pin "2") (pinfunction "PSEL_2") (pintype "output"))
    )
    (net (code "23") (name "Net-(U$3-PG)") (class "Default")
      (node (ref "R19") (pin "2") (pinfunction "2_2") (pintype "passive"))
      (node (ref "R20") (pin "1") (pinfunction "1_1") (pintype "passive"))
      (node (ref "R26") (pin "1") (pinfunction "1_1") (pintype "passive"))
      (node (ref "U$3") (pin "14") (pinfunction "PG_14") (pintype "bidirectional"))
    )
    (net (code "24") (name "Net-(U$3-PS)") (class "Default")
      (node (ref "R23") (pin "2") (pinfunction "2_2") (pintype "passive"))
      (node (ref "R24") (pin "1") (pinfunction "1_1") (pintype "passive"))
      (node (ref "U$3") (pin "13") (pinfunction "PS_13") (pintype "bidirectional"))
    )
    (net (code "25") (name "Net-(U$6-MODE)") (class "Default")
      (node (ref "R16") (pin "2") (pinfunction "2_2") (pintype "passive"))
      (node (ref "R18") (pin "1") (pinfunction "1_1") (pintype "passive"))
      (node (ref "U$6") (pin "B2") (pinfunction "MODE_B2") (pintype "bidirectional"))
    )
    (net (code "26") (name "Net-(U1-~{QON})") (class "Default")
      (node (ref "R1") (pin "1") (pinfunction "1_1") (pintype "passive"))
      (node (ref "U1") (pin "12") (pinfunction "~{QON}_12") (pintype "bidirectional"))
    )
    (net (code "27") (name "Net-(U4-CELL)") (class "Default")
      (node (ref "C6") (pin "1") (pinfunction "1_1") (pintype "bidirectional"))
      (node (ref "R54") (pin "2") (pinfunction "2_2") (pintype "passive"))
      (node (ref "U4") (pin "2") (pinfunction "CELL_2") (pintype "bidirectional"))
    )
    (net (code "28") (name "Net-(U4-VDD)") (class "Default")
      (node (ref "C5") (pin "1") (pinfunction "1_1") (pintype "bidirectional"))
      (node (ref "R7") (pin "2") (pinfunction "2_2") (pintype "passive"))
      (node (ref "U4") (pin "3") (pinfunction "VDD_3") (pintype "bidirectional"))
    )
    (net (code "29") (name "OTG") (class "Default")
      (node (ref "R3") (pin "2") (pinfunction "2_2") (pintype "passive"))
      (node (ref "U1") (pin "8") (pinfunction "OTG_8") (pintype "bidirectional"))
    )
    (net (code "30") (name "PG") (class "Default")
      (node (ref "CONN1") (pin "11") (pinfunction "11_11") (pintype "passive"))
      (node (ref "R26") (pin "2") (pinfunction "2_2") (pintype "passive"))
      (node (ref "U$4") (pin "11") (pinfunction "11_11") (pintype "bidirectional"))
      (node (ref "U$4") (pin "P$11") (pinfunction "11_P$11") (pintype "bidirectional"))
    )
    (net (code "31") (name "PMID") (class "Default")
      (node (ref "C17") (pin "2") (pinfunction "2_2") (pintype "bidirectional"))
      (node (ref "C49") (pin "1") (pinfunction "1_1") (pintype "bidirectional"))
      (node (ref "C7") (pin "1") (pinfunction "1_1") (pintype "bidirectional"))
      (node (ref "C74") (pin "2") (pinfunction "2_2") (pintype "bidirectional"))
      (node (ref "U1") (pin "23") (pinfunction "PMID_23") (pintype "passive"))
    )
    (net (code "32") (name "REGN") (class "Default")
      (node (ref "C37") (pin "1") (pinfunction "1_1") (pintype "bidirectional"))
      (node (ref "CONN2") (pin "6") (pinfunction "6_6") (pintype "passive"))
      (node (ref "R35") (pin "1") (pinfunction "1_1") (pintype "passive"))
      (node (ref "U$1") (pin "7") (pinfunction "7_7") (pintype "bidirectional"))
      (node (ref "U$1") (pin "P$7") (pinfunction "7_P$7") (pintype "bidirectional"))
      (node (ref "U1") (pin "22") (pinfunction "REGN_22") (pintype "bidirectional"))
    )
    (net (code "33") (name "SCL") (class "Default")
      (node (ref "CONN1") (pin "1") (pinfunction "1_1") (pintype "passive"))
      (node (ref "R30") (pin "2") (pinfunction "2_2") (pintype "passive"))
      (node (ref "U$4") (pin "1") (pinfunction "1_1") (pintype "bidirectional"))
      (node (ref "U$4") (pin "P$1") (pinfunction "1_P$1") (pintype "bidirectional"))
      (node (ref "U1") (pin "5") (pinfunction "SCL_5") (pintype "output"))
      (node (ref "U4") (pin "7") (pinfunction "SCL_7") (pintype "bidirectional"))
    )
    (net (code "34") (name "SDA") (class "Default")
      (node (ref "CONN1") (pin "2") (pinfunction "2_2") (pintype "passive"))
      (node (ref "R36") (pin "2") (pinfunction "2_2") (pintype "passive"))
      (node (ref "U$4") (pin "2") (pinfunction "2_2") (pintype "bidirectional"))
      (node (ref "U$4") (pin "P$2") (pinfunction "2_P$2") (pintype "bidirectional"))
      (node (ref "U1") (pin "6") (pinfunction "SDA_6") (pintype "bidirectional"))
      (node (ref "U4") (pin "8") (pinfunction "SDA_8") (pintype "bidirectional"))
    )
    (net (code "35") (name "SW1") (class "Default")
      (node (ref "C2") (pin "2") (pinfunction "2_2") (pintype "bidirectional"))
      (node (ref "L7") (pin "P$1") (pinfunction "1_P$1") (pintype "passive"))
      (node (ref "U1") (pin "19") (pinfunction "SW_19") (pintype "power_in"))
      (node (ref "U1") (pin "20") (pinfunction "SW_20") (pintype "power_in"))
    )
    (net (code "36") (name "TS") (class "Default")
      (node (ref "CONN1") (pin "4") (pinfunction "4_4") (pintype "passive"))
      (node (ref "R1") (pin "2") (pinfunction "2_2") (pintype "passive"))
      (node (ref "R34") (pin "1") (pinfunction "1_1") (pintype "passive"))
      (node (ref "R35") (pin "2") (pinfunction "2_2") (pintype "passive"))
      (node (ref "U$4") (pin "4") (pinfunction "4_4") (pintype "bidirectional"))
      (node (ref "U$4") (pin "P$4") (pinfunction "4_P$4") (pintype "bidirectional"))
      (node (ref "U1") (pin "11") (pinfunction "TS_11") (pintype "bidirectional"))
    )
    (net (code "37") (name "VBAT") (class "Default")
      (node (ref "C3") (pin "1") (pinfunction "1_1") (pintype "bidirectional"))
      (node (ref "C72") (pin "1") (pinfunction "1_1") (pintype "bidirectional"))
      (node (ref "C73") (pin "1") (pinfunction "1_1") (pintype "bidirectional"))
      (node (ref "CONN1") (pin "5") (pinfunction "5_5") (pintype "passive"))
      (node (ref "CONN1") (pin "6") (pinfunction "6_6") (pintype "passive"))
      (node (ref "CONN1") (pin "7") (pinfunction "7_7") (pintype "passive"))
      (node (ref "R54") (pin "1") (pinfunction "1_1") (pintype "passive"))
      (node (ref "U$4") (pin "5") (pinfunction "5_5") (pintype "bidirectional"))
      (node (ref "U$4") (pin "6") (pinfunction "6_6") (pintype "bidirectional"))
      (node (ref "U$4") (pin "7") (pinfunction "7_7") (pintype "bidirectional"))
      (node (ref "U$4") (pin "P$5") (pinfunction "5_P$5") (pintype "bidirectional"))
      (node (ref "U$4") (pin "P$6") (pinfunction "6_P$6") (pintype "bidirectional"))
      (node (ref "U$4") (pin "P$7") (pinfunction "7_P$7") (pintype "bidirectional"))
      (node (ref "U1") (pin "13") (pinfunction "BAT_13") (pintype "passive"))
      (node (ref "U1") (pin "14") (pinfunction "BAT_14") (pintype "power_in"))
    )
    (net (code "38") (name "VCC") (class "Default")
      (node (ref "C28") (pin "2") (pinfunction "P$2_2") (pintype "passive"))
      (node (ref "C29") (pin "1") (pinfunction "1_1") (pintype "bidirectional"))
      (node (ref "C30") (pin "1") (pinfunction "1_1") (pintype "bidirectional"))
      (node (ref "C31") (pin "1") (pinfunction "1_1") (pintype "bidirectional"))
      (node (ref "C32") (pin "1") (pinfunction "1_1") (pintype "bidirectional"))
      (node (ref "C34") (pin "1") (pinfunction "1_1") (pintype "bidirectional"))
      (node (ref "C35") (pin "1") (pinfunction "1_1") (pintype "bidirectional"))
      (node (ref "CONN2") (pin "7") (pinfunction "7_7") (pintype "passive"))
      (node (ref "CONN2") (pin "8") (pinfunction "8_8") (pintype "passive"))
      (node (ref "R11") (pin "2") (pinfunction "2_2") (pintype "passive"))
      (node (ref "R19") (pin "1") (pinfunction "1_1") (pintype "passive"))
      (node (ref "R4") (pin "2") (pinfunction "2_2") (pintype "passive"))
      (node (ref "U$1") (pin "5") (pinfunction "5_5") (pintype "bidirectional"))
      (node (ref "U$1") (pin "6") (pinfunction "6_6") (pintype "bidirectional"))
      (node (ref "U$1") (pin "P$5") (pinfunction "5_P$5") (pintype "bidirectional"))
      (node (ref "U$1") (pin "P$6") (pinfunction "6_P$6") (pintype "bidirectional"))
      (node (ref "U$3") (pin "4") (pinfunction "VOUT1_4") (pintype "bidirectional"))
      (node (ref "U$3") (pin "5") (pinfunction "VOUT2_5") (pintype "bidirectional"))
    )
    (net (code "39") (name "VIN") (class "Default")
      (node (ref "C10") (pin "2") (pinfunction "P$2_2") (pintype "passive"))
      (node (ref "C11") (pin "2") (pinfunction "P$2_2") (pintype "passive"))
      (node (ref "C20") (pin "2") (pinfunction "P$2_2") (pintype "passive"))
      (node (ref "C57") (pin "1") (pinfunction "1_1") (pintype "bidirectional"))
      (node (ref "C64") (pin "1") (pinfunction "1_1") (pintype "bidirectional"))
      (node (ref "C9") (pin "2") (pinfunction "P$2_2") (pintype "passive"))
      (node (ref "CONN2") (pin "1") (pinfunction "1_1") (pintype "passive"))
      (node (ref "CONN2") (pin "2") (pinfunction "2_2") (pintype "passive"))
      (node (ref "U$1") (pin "11") (pinfunction "11_11") (pintype "bidirectional"))
      (node (ref "U$1") (pin "12") (pinfunction "12_12") (pintype "bidirectional"))
      (node (ref "U$1") (pin "P$11") (pinfunction "11_P$11") (pintype "bidirectional"))
      (node (ref "U$1") (pin "P$12") (pinfunction "12_P$12") (pintype "bidirectional"))
      (node (ref "U1") (pin "1") (pinfunction "VBUS_1") (pintype "power_in"))
      (node (ref "U1") (pin "24") (pinfunction "VBUS_24") (pintype "passive"))
    )
    (net (code "40") (name "VSYS") (class "Default")
      (node (ref "C1") (pin "2") (pinfunction "P$2_2") (pintype "passive"))
      (node (ref "C12") (pin "1") (pinfunction "1_1") (pintype "bidirectional"))
      (node (ref "C13") (pin "2") (pinfunction "P$2_2") (pintype "passive"))
      (node (ref "C21") (pin "2") (pinfunction "P$2_2") (pintype "passive"))
      (node (ref "C22") (pin "1") (pinfunction "1_1") (pintype "bidirectional"))
      (node (ref "C26") (pin "1") (pinfunction "1_1") (pintype "bidirectional"))
      (node (ref "C27") (pin "2") (pinfunction "P$2_2") (pintype "passive"))
      (node (ref "C33") (pin "1") (pinfunction "1_1") (pintype "bidirectional"))
      (node (ref "C4") (pin "2") (pinfunction "P$2_2") (pintype "passive"))
      (node (ref "C58") (pin "1") (pinfunction "1_1") (pintype "bidirectional"))
      (node (ref "C59") (pin "1") (pinfunction "1_1") (pintype "bidirectional"))
      (node (ref "C8") (pin "2") (pinfunction "P$2_2") (pintype "passive"))
      (node (ref "L7") (pin "P$2") (pinfunction "2_P$2") (pintype "passive"))
      (node (ref "R14") (pin "1") (pinfunction "1_1") (pintype "passive"))
      (node (ref "R16") (pin "1") (pinfunction "1_1") (pintype "passive"))
      (node (ref "R21") (pin "1") (pinfunction "1_1") (pintype "passive"))
      (node (ref "R23") (pin "1") (pinfunction "1_1") (pintype "passive"))
      (node (ref "U$3") (pin "10") (pinfunction "VIN1_10") (pintype "bidirectional"))
      (node (ref "U$3") (pin "11") (pinfunction "VIN2_11") (pintype "bidirectional"))
      (node (ref "U$6") (pin "A1") (pinfunction "VIN_A1") (pintype "bidirectional"))
      (node (ref "U1") (pin "15") (pinfunction "SYS_15") (pintype "power_in"))
      (node (ref "U1") (pin "16") (pinfunction "SYS_16") (pintype "power_in"))
    )
    (net (code "41") (name "unconnected-(U2-EN-Pad5)") (class "Default")
      (node (ref "U2") (pin "5") (pinfunction "EN_5") (pintype "bidirectional"))
    )
    (net (code "42") (name "unconnected-(U2-FB-Pad8)") (class "Default")
      (node (ref "U2") (pin "8") (pinfunction "FB_8") (pintype "bidirectional"))
    )
    (net (code "43") (name "unconnected-(U2-GND-Pad7)") (class "Default")
      (node (ref "U2") (pin "7") (pinfunction "GND_7") (pintype "bidirectional"))
    )
    (net (code "44") (name "unconnected-(U2-LX1-Pad3)") (class "Default")
      (node (ref "U2") (pin "3") (pinfunction "LX1_3") (pintype "bidirectional"))
    )
    (net (code "45") (name "unconnected-(U2-LX2-Pad2)") (class "Default")
      (node (ref "U2") (pin "2") (pinfunction "LX2_2") (pintype "bidirectional"))
    )
    (net (code "46") (name "unconnected-(U2-MODE-Pad6)") (class "Default")
      (node (ref "U2") (pin "6") (pinfunction "MODE_6") (pintype "bidirectional"))
    )
    (net (code "47") (name "unconnected-(U2-OUT-Pad1)") (class "Default")
      (node (ref "U2") (pin "1") (pinfunction "OUT_1") (pintype "bidirectional"))
    )
    (net (code "48") (name "unconnected-(U2-VIN-Pad4)") (class "Default")
      (node (ref "U2") (pin "4") (pinfunction "VIN_4") (pintype "bidirectional"))
    )
    (net (code "49") (name "~{CE}") (class "Default")
      (node (ref "R10") (pin "2") (pinfunction "2_2") (pintype "passive"))
      (node (ref "U1") (pin "9") (pinfunction "~{CE}_9") (pintype "output"))
    )
    (net (code "50") (name "~{FUEL-INT}") (class "Default")
      (node (ref "CONN1") (pin "3") (pinfunction "3_3") (pintype "passive"))
      (node (ref "R2") (pin "2") (pinfunction "2_2") (pintype "passive"))
      (node (ref "U$4") (pin "3") (pinfunction "3_3") (pintype "bidirectional"))
      (node (ref "U$4") (pin "P$3") (pinfunction "3_P$3") (pintype "bidirectional"))
      (node (ref "U1") (pin "7") (pinfunction "INT_7") (pintype "bidirectional"))
      (node (ref "U4") (pin "5") (pinfunction "ALT_5") (pintype "bidirectional"))
    )
    (net (code "51") (name "~{RST}") (class "Default")
      (node (ref "CONN1") (pin "10") (pinfunction "10_10") (pintype "passive"))
      (node (ref "U$4") (pin "10") (pinfunction "10_10") (pintype "bidirectional"))
      (node (ref "U$4") (pin "P$10") (pinfunction "10_P$10") (pintype "bidirectional"))
    )
  )
)
